# sfp_wrapper.net
KiCad netlist of a schematic drawn in Altium Designer
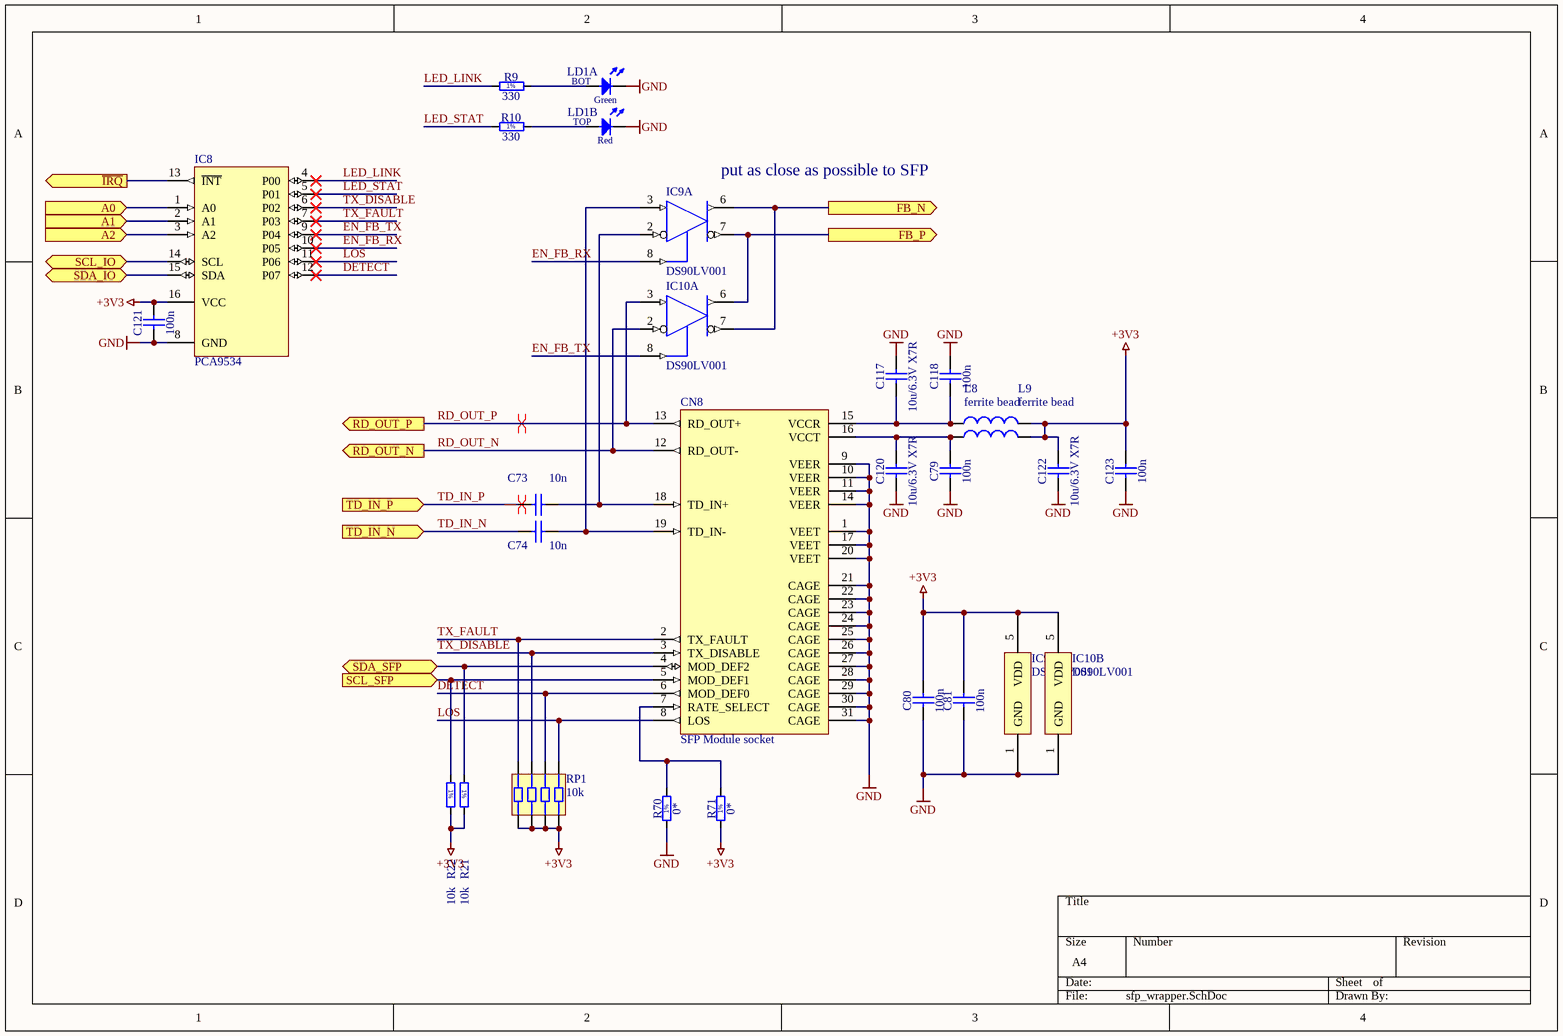
[diagram p0: sfp_wrapper.SchDoc]

(export (version "E")
  (design (tool "Eeschema 10.0.6"))
  (components
    (comp (ref "C73")
      (value "10n")
      (footprint "CAPC1608X87N")
      (description "Non-polarised capacitor")
      (fields
        (field (name "PART NUMBER") "CC0603_10NF_50V_10%_X7R")
        (field (name "VOLTAGE") "50V")
        (field (name "AUTHOR") "CERN DEM JLC")
      )
      (libsource (lib "Capacitors") (part "Capacitor - non polarized"))
    )
    (comp (ref "C74")
      (value "10n")
      (footprint "CAPC1608X87N")
      (description "Non-polarised capacitor")
      (fields
        (field (name "PART NUMBER") "CC0603_10NF_50V_10%_X7R")
        (field (name "VOLTAGE") "50V")
        (field (name "AUTHOR") "CERN DEM JLC")
      )
      (libsource (lib "Capacitors") (part "Capacitor - non polarized"))
    )
    (comp (ref "C79")
      (value "100n")
      (footprint "CAPC1608X87N")
      (description "Non-polarised capacitor")
      (fields
        (field (name "PART NUMBER") "CC0603_100NF_50V_10%_X7R")
        (field (name "VOLTAGE") "50V")
        (field (name "AUTHOR") "CERN DEM JLC")
      )
      (libsource (lib "Capacitors") (part "Capacitor - non polarized"))
    )
    (comp (ref "C80")
      (value "100n")
      (footprint "CAPC1608X87N")
      (description "Non-polarised capacitor")
      (fields
        (field (name "PART NUMBER") "CC0603_100NF_50V_10%_X7R")
        (field (name "VOLTAGE") "50V")
        (field (name "AUTHOR") "CERN DEM JLC")
      )
      (libsource (lib "Capacitors") (part "Capacitor - non polarized"))
    )
    (comp (ref "C81")
      (value "100n")
      (footprint "CAPC1608X87N")
      (description "Non-polarised capacitor")
      (fields
        (field (name "PART NUMBER") "CC0603_100NF_50V_10%_X7R")
        (field (name "VOLTAGE") "50V")
        (field (name "AUTHOR") "CERN DEM JLC")
      )
      (libsource (lib "Capacitors") (part "Capacitor - non polarized"))
    )
    (comp (ref "C117")
      (value "10u/6.3V X7R")
      (footprint "CAPC3216X140N")
      (description "Non-polarised capacitor")
      (fields
        (field (name "PART NUMBER") "CC1206_10UF_10V_10%_X7R")
        (field (name "VOLTAGE") "10V")
        (field (name "AUTHOR") "CERN DEM JLC")
      )
      (libsource (lib "Capacitors") (part "Capacitor - non polarized"))
    )
    (comp (ref "C118")
      (value "100n")
      (footprint "CAPC1608X87N")
      (description "Non-polarised capacitor")
      (fields
        (field (name "PART NUMBER") "CC0603_100NF_50V_10%_X7R")
        (field (name "VOLTAGE") "50V")
        (field (name "AUTHOR") "CERN DEM JLC")
      )
      (libsource (lib "Capacitors") (part "Capacitor - non polarized"))
    )
    (comp (ref "C120")
      (value "10u/6.3V X7R")
      (footprint "CAPC3216X140N")
      (description "Non-polarised capacitor")
      (fields
        (field (name "PART NUMBER") "CC1206_10UF_10V_10%_X7R")
        (field (name "VOLTAGE") "10V")
        (field (name "AUTHOR") "CERN DEM JLC")
      )
      (libsource (lib "Capacitors") (part "Capacitor - non polarized"))
    )
    (comp (ref "C121")
      (value "100n")
      (footprint "CAPC1608X87N")
      (description "Non-polarised capacitor")
      (fields
        (field (name "PART NUMBER") "CC0603_100NF_50V_10%_X7R")
        (field (name "VOLTAGE") "50V")
        (field (name "AUTHOR") "CERN DEM JLC")
      )
      (libsource (lib "Capacitors") (part "Capacitor - non polarized"))
    )
    (comp (ref "C122")
      (value "10u/6.3V X7R")
      (footprint "CAPC3216X140N")
      (description "Non-polarised capacitor")
      (fields
        (field (name "PART NUMBER") "CC1206_10UF_10V_10%_X7R")
        (field (name "VOLTAGE") "10V")
        (field (name "AUTHOR") "CERN DEM JLC")
      )
      (libsource (lib "Capacitors") (part "Capacitor - non polarized"))
    )
    (comp (ref "C123")
      (value "100n")
      (footprint "CAPC1608X87N")
      (description "Non-polarised capacitor")
      (fields
        (field (name "PART NUMBER") "CC0603_100NF_50V_10%_X7R")
        (field (name "VOLTAGE") "50V")
        (field (name "AUTHOR") "CERN DEM JLC")
      )
      (libsource (lib "Capacitors") (part "Capacitor - non polarized"))
    )
    (comp (ref "CN8")
      (value "SFP Module socket")
      (footprint "SFP_SINGLE_PORT")
      (description "Socket for SFP module")
      (libsource (lib "wr_switch") (part "SFP_SOCKET_SINGLE"))
    )
    (comp (ref "IC8")
      (value "PCA9534")
      (footprint "TSOP65P640-16AM")
      (description "8-bit I2C I/O expander")
      (libsource (lib "wr_switch") (part "PCA9534"))
    )
    (comp (ref "IC9")
      (value "DS90LV001")
      (footprint "SOIC127P600-8AL")
      (description "LVDS buffer with enable")
      (libsource (lib "wr_switch") (part "DS90LV001"))
    )
    (comp (ref "IC10")
      (value "DS90LV001")
      (footprint "SOIC127P600-8AL")
      (description "LVDS buffer with enable")
      (libsource (lib "wr_switch") (part "DS90LV001"))
    )
    (comp (ref "L8")
      (value "ferrite bead")
      (footprint "INDC2012-0805")
      (description "Ferrite bead")
      (fields (field (name "Comment") "Inductor") (field (name "PUBLISHER") "Altium Limited"))
      (libsource (lib "Miscellaneous Devices") (part "Inductor"))
    )
    (comp (ref "L9")
      (value "ferrite bead")
      (footprint "INDC2012-0805")
      (description "Ferrite bead")
      (fields (field (name "Comment") "Inductor") (field (name "PUBLISHER") "Altium Limited"))
      (libsource (lib "Miscellaneous Devices") (part "Inductor"))
    )
    (comp (ref "LD1")
      (value "Red/Green")
      (footprint "LED_DIALIGHT_571-0112-100F")
      (description "2x LED  Botom Green, Top Red")
      (fields
        (field (name "PART NUMBER") "LED_DIALIGHT_571-0112-100F")
        (field (name "MANUFACTURER") "DIALIGHT")
        (field (name "AUTHOR") "CERN DEM JLC")
      )
      (libsource (lib "ICs And Semiconductors") (part "LED x2 G-1C2A-BOT_R-3C4A-TOP"))
    )
    (comp (ref "R9")
      (value "330")
      (footprint "RESC1608X55N")
      (description "Resistor - 1%")
      (fields
        (field (name "PART NUMBER") "R0603_330R_1%_0.1W_100PPM")
        (field (name "POWER") "0.1W")
        (field (name "AUTHOR") "CERN DEM JLC")
      )
      (libsource (lib "Resistors") (part "Resistor - 1%"))
    )
    (comp (ref "R10")
      (value "330")
      (footprint "RESC1608X55N")
      (description "Resistor - 1%")
      (fields
        (field (name "PART NUMBER") "R0603_330R_1%_0.1W_100PPM")
        (field (name "POWER") "0.1W")
        (field (name "AUTHOR") "CERN DEM JLC")
      )
      (libsource (lib "Resistors") (part "Resistor - 1%"))
    )
    (comp (ref "R21")
      (value "10k")
      (footprint "RESC1608X55N")
      (description "Resistor - 1%")
      (fields
        (field (name "PART NUMBER") "R0603_10K_1%_0.1W_100PPM")
        (field (name "POWER") "0.1W")
        (field (name "AUTHOR") "CERN DEM JLC")
      )
      (libsource (lib "Resistors") (part "Resistor - 1%"))
    )
    (comp (ref "R22")
      (value "10k")
      (footprint "RESC1608X55N")
      (description "Resistor - 1%")
      (fields
        (field (name "PART NUMBER") "R0603_10K_1%_0.1W_100PPM")
        (field (name "POWER") "0.1W")
        (field (name "AUTHOR") "CERN DEM JLC")
      )
      (libsource (lib "Resistors") (part "Resistor - 1%"))
    )
    (comp (ref "R70")
      (value "0*")
      (footprint "RESC1608X55N")
      (description "Resistor - 1%")
      (fields
        (field (name "PART NUMBER") "R0603_0R_JUMPER")
        (field (name "MANUFACTURER") "GENERIC")
        (field (name "AUTHOR") "CERN DEM JLC")
      )
      (libsource (lib "Resistors") (part "Resistor - 1%"))
    )
    (comp (ref "R71")
      (value "0*")
      (footprint "RESC1608X55N")
      (description "Resistor - 1%")
      (fields
        (field (name "PART NUMBER") "R0603_0R_JUMPER")
        (field (name "MANUFACTURER") "GENERIC")
        (field (name "AUTHOR") "CERN DEM JLC")
      )
      (libsource (lib "Resistors") (part "Resistor - 1%"))
    )
    (comp (ref "RP1")
      (value "10k")
      (footprint "CAY-16")
      (description "Resistor network 1206 (4x0402) Maritex RAC4Xxxx")
      (libsource (lib "LIBRARY_SCH") (part "RES_ARRAY_1206"))
    )
  )
  (nets
    (net (code "1") (name "+3V3") (class "Default")
      (node (ref "C121") (pin "2") (pinfunction "2_2") (pintype "passive"))
      (node (ref "C122") (pin "2") (pinfunction "2_2") (pintype "passive"))
      (node (ref "C123") (pin "2") (pinfunction "2_2") (pintype "passive"))
      (node (ref "C80") (pin "2") (pinfunction "2_2") (pintype "passive"))
      (node (ref "C81") (pin "2") (pinfunction "2_2") (pintype "passive"))
      (node (ref "IC10") (pin "5") (pinfunction "VDD_5") (pintype "power_in"))
      (node (ref "IC8") (pin "16") (pinfunction "VCC_16") (pintype "power_in"))
      (node (ref "IC9") (pin "5") (pinfunction "VDD_5") (pintype "power_in"))
      (node (ref "L8") (pin "2") (pinfunction "2_2") (pintype "passive"))
      (node (ref "L9") (pin "2") (pinfunction "2_2") (pintype "passive"))
      (node (ref "R21") (pin "2") (pinfunction "2_2") (pintype "passive"))
      (node (ref "R22") (pin "2") (pinfunction "2_2") (pintype "passive"))
      (node (ref "R71") (pin "1") (pinfunction "1_1") (pintype "passive"))
      (node (ref "RP1") (pin "1") (pinfunction "1_1") (pintype "passive"))
      (node (ref "RP1") (pin "2") (pinfunction "2_2") (pintype "passive"))
      (node (ref "RP1") (pin "3") (pinfunction "3_3") (pintype "passive"))
      (node (ref "RP1") (pin "4") (pinfunction "4_4") (pintype "passive"))
    )
    (net (code "2") (name "/A0") (class "Default")
      (node (ref "IC8") (pin "1") (pinfunction "A0_1") (pintype "input"))
    )
    (net (code "3") (name "/A1") (class "Default")
      (node (ref "IC8") (pin "2") (pinfunction "A1_2") (pintype "input"))
    )
    (net (code "4") (name "/A2") (class "Default")
      (node (ref "IC8") (pin "3") (pinfunction "A2_3") (pintype "input"))
    )
    (net (code "5") (name "/DETECT") (class "Default")
      (node (ref "CN8") (pin "6") (pinfunction "MOD_DEF0_6") (pintype "output"))
      (node (ref "IC8") (pin "12") (pinfunction "P07_12") (pintype "bidirectional"))
      (node (ref "RP1") (pin "6") (pinfunction "6_6") (pintype "passive"))
    )
    (net (code "6") (name "/EN_FB_RX") (class "Default")
      (node (ref "IC8") (pin "10") (pinfunction "P05_10") (pintype "bidirectional"))
      (node (ref "IC9") (pin "8") (pinfunction "EN_8") (pintype "input"))
    )
    (net (code "7") (name "/EN_FB_TX") (class "Default")
      (node (ref "IC10") (pin "8") (pinfunction "EN_8") (pintype "input"))
      (node (ref "IC8") (pin "9") (pinfunction "P04_9") (pintype "bidirectional"))
    )
    (net (code "8") (name "/FB_N") (class "Default")
      (node (ref "IC10") (pin "7") (pinfunction "OUT-_7") (pintype "output"))
      (node (ref "IC9") (pin "6") (pinfunction "OUT+_6") (pintype "output"))
    )
    (net (code "9") (name "/FB_P") (class "Default")
      (node (ref "IC10") (pin "6") (pinfunction "OUT+_6") (pintype "output"))
      (node (ref "IC9") (pin "7") (pinfunction "OUT-_7") (pintype "output"))
    )
    (net (code "10") (name "/LED_LINK") (class "Default")
      (node (ref "IC8") (pin "4") (pinfunction "P00_4") (pintype "bidirectional"))
      (node (ref "R9") (pin "1") (pinfunction "1_1") (pintype "passive"))
    )
    (net (code "11") (name "/LED_STAT") (class "Default")
      (node (ref "IC8") (pin "5") (pinfunction "P01_5") (pintype "bidirectional"))
      (node (ref "R10") (pin "1") (pinfunction "1_1") (pintype "passive"))
    )
    (net (code "12") (name "/LOS") (class "Default")
      (node (ref "CN8") (pin "8") (pinfunction "LOS_8") (pintype "output"))
      (node (ref "IC8") (pin "11") (pinfunction "P06_11") (pintype "bidirectional"))
      (node (ref "RP1") (pin "5") (pinfunction "5_5") (pintype "passive"))
    )
    (net (code "13") (name "/RD_OUT_N") (class "Default")
      (node (ref "CN8") (pin "12") (pinfunction "RD_OUT-_12") (pintype "output"))
      (node (ref "IC10") (pin "2") (pinfunction "IN-_2") (pintype "input"))
    )
    (net (code "14") (name "/RD_OUT_P") (class "Default")
      (node (ref "CN8") (pin "13") (pinfunction "RD_OUT+_13") (pintype "output"))
      (node (ref "IC10") (pin "3") (pinfunction "IN+_3") (pintype "input"))
    )
    (net (code "15") (name "/SCL_IO") (class "Default")
      (node (ref "IC8") (pin "14") (pinfunction "SCL_14") (pintype "bidirectional"))
    )
    (net (code "16") (name "/SCL_SFP") (class "Default")
      (node (ref "CN8") (pin "5") (pinfunction "MOD_DEF1_5") (pintype "input"))
      (node (ref "R22") (pin "1") (pinfunction "1_1") (pintype "passive"))
    )
    (net (code "17") (name "/SDA_IO") (class "Default")
      (node (ref "IC8") (pin "15") (pinfunction "SDA_15") (pintype "bidirectional"))
    )
    (net (code "18") (name "/SDA_SFP") (class "Default")
      (node (ref "CN8") (pin "4") (pinfunction "MOD_DEF2_4") (pintype "bidirectional"))
      (node (ref "R21") (pin "1") (pinfunction "1_1") (pintype "passive"))
    )
    (net (code "19") (name "/TD_IN_N") (class "Default")
      (node (ref "C74") (pin "1") (pinfunction "1_1") (pintype "passive"))
    )
    (net (code "20") (name "/TD_IN_P") (class "Default")
      (node (ref "C73") (pin "1") (pinfunction "1_1") (pintype "passive"))
    )
    (net (code "21") (name "/TX_DISABLE") (class "Default")
      (node (ref "CN8") (pin "3") (pinfunction "TX_DISABLE_3") (pintype "input"))
      (node (ref "IC8") (pin "6") (pinfunction "P02_6") (pintype "bidirectional"))
      (node (ref "RP1") (pin "7") (pinfunction "7_7") (pintype "passive"))
    )
    (net (code "22") (name "/TX_FAULT") (class "Default")
      (node (ref "CN8") (pin "2") (pinfunction "TX_FAULT_2") (pintype "output"))
      (node (ref "IC8") (pin "7") (pinfunction "P03_7") (pintype "bidirectional"))
      (node (ref "RP1") (pin "8") (pinfunction "8_8") (pintype "passive"))
    )
    (net (code "23") (name "/~{IRQ}") (class "Default")
      (node (ref "IC8") (pin "13") (pinfunction "~{INT}_13") (pintype "output"))
    )
    (net (code "24") (name "GND") (class "Default")
      (node (ref "C117") (pin "2") (pinfunction "2_2") (pintype "passive"))
      (node (ref "C118") (pin "2") (pinfunction "2_2") (pintype "passive"))
      (node (ref "C120") (pin "1") (pinfunction "1_1") (pintype "passive"))
      (node (ref "C121") (pin "1") (pinfunction "1_1") (pintype "passive"))
      (node (ref "C122") (pin "1") (pinfunction "1_1") (pintype "passive"))
      (node (ref "C123") (pin "1") (pinfunction "1_1") (pintype "passive"))
      (node (ref "C79") (pin "1") (pinfunction "1_1") (pintype "passive"))
      (node (ref "C80") (pin "1") (pinfunction "1_1") (pintype "passive"))
      (node (ref "C81") (pin "1") (pinfunction "1_1") (pintype "passive"))
      (node (ref "CN8") (pin "1") (pinfunction "VEET_1") (pintype "power_in"))
      (node (ref "CN8") (pin "10") (pinfunction "VEER_10") (pintype "power_in"))
      (node (ref "CN8") (pin "11") (pinfunction "VEER_11") (pintype "power_in"))
      (node (ref "CN8") (pin "14") (pinfunction "VEER_14") (pintype "power_in"))
      (node (ref "CN8") (pin "17") (pinfunction "VEET_17") (pintype "power_in"))
      (node (ref "CN8") (pin "20") (pinfunction "VEET_20") (pintype "power_in"))
      (node (ref "CN8") (pin "21") (pinfunction "CAGE_21") (pintype "power_in"))
      (node (ref "CN8") (pin "22") (pinfunction "CAGE_22") (pintype "power_in"))
      (node (ref "CN8") (pin "23") (pinfunction "CAGE_23") (pintype "power_in"))
      (node (ref "CN8") (pin "24") (pinfunction "CAGE_24") (pintype "power_in"))
      (node (ref "CN8") (pin "25") (pinfunction "CAGE_25") (pintype "power_in"))
      (node (ref "CN8") (pin "26") (pinfunction "CAGE_26") (pintype "power_in"))
      (node (ref "CN8") (pin "27") (pinfunction "CAGE_27") (pintype "power_in"))
      (node (ref "CN8") (pin "28") (pinfunction "CAGE_28") (pintype "power_in"))
      (node (ref "CN8") (pin "29") (pinfunction "CAGE_29") (pintype "power_in"))
      (node (ref "CN8") (pin "30") (pinfunction "CAGE_30") (pintype "power_in"))
      (node (ref "CN8") (pin "31") (pinfunction "CAGE_31") (pintype "power_in"))
      (node (ref "CN8") (pin "9") (pinfunction "VEER_9") (pintype "power_in"))
      (node (ref "IC10") (pin "1") (pinfunction "GND_1") (pintype "power_in"))
      (node (ref "IC8") (pin "8") (pinfunction "GND_8") (pintype "power_in"))
      (node (ref "IC9") (pin "1") (pinfunction "GND_1") (pintype "power_in"))
      (node (ref "LD1") (pin "1") (pinfunction "C_1") (pintype "passive"))
      (node (ref "LD1") (pin "3") (pinfunction "C_3") (pintype "passive"))
      (node (ref "R70") (pin "1") (pinfunction "1_1") (pintype "passive"))
    )
    (net (code "25") (name "Net-(CN8-RATE_SELECT)") (class "Default")
      (node (ref "CN8") (pin "7") (pinfunction "RATE_SELECT_7") (pintype "input"))
      (node (ref "R70") (pin "2") (pinfunction "2_2") (pintype "passive"))
      (node (ref "R71") (pin "2") (pinfunction "2_2") (pintype "passive"))
    )
    (net (code "26") (name "Net-(CN8-TD_IN+)") (class "Default")
      (node (ref "C73") (pin "2") (pinfunction "2_2") (pintype "passive"))
      (node (ref "CN8") (pin "18") (pinfunction "TD_IN+_18") (pintype "input"))
      (node (ref "IC9") (pin "2") (pinfunction "IN-_2") (pintype "input"))
    )
    (net (code "27") (name "Net-(CN8-TD_IN-)") (class "Default")
      (node (ref "C74") (pin "2") (pinfunction "2_2") (pintype "passive"))
      (node (ref "CN8") (pin "19") (pinfunction "TD_IN-_19") (pintype "input"))
      (node (ref "IC9") (pin "3") (pinfunction "IN+_3") (pintype "input"))
    )
    (net (code "28") (name "Net-(CN8-VCCR)") (class "Default")
      (node (ref "C117") (pin "1") (pinfunction "1_1") (pintype "passive"))
      (node (ref "C118") (pin "1") (pinfunction "1_1") (pintype "passive"))
      (node (ref "CN8") (pin "15") (pinfunction "VCCR_15") (pintype "power_in"))
      (node (ref "L9") (pin "1") (pinfunction "1_1") (pintype "passive"))
    )
    (net (code "29") (name "Net-(CN8-VCCT)") (class "Default")
      (node (ref "C120") (pin "2") (pinfunction "2_2") (pintype "passive"))
      (node (ref "C79") (pin "2") (pinfunction "2_2") (pintype "passive"))
      (node (ref "CN8") (pin "16") (pinfunction "VCCT_16") (pintype "power_in"))
      (node (ref "L8") (pin "1") (pinfunction "1_1") (pintype "passive"))
    )
    (net (code "30") (name "Net-(LD1A-A)") (class "Default")
      (node (ref "LD1") (pin "2") (pinfunction "A_2") (pintype "passive"))
      (node (ref "R9") (pin "2") (pinfunction "2_2") (pintype "passive"))
    )
    (net (code "31") (name "Net-(LD1B-A)") (class "Default")
      (node (ref "LD1") (pin "4") (pinfunction "A_4") (pintype "passive"))
      (node (ref "R10") (pin "2") (pinfunction "2_2") (pintype "passive"))
    )
  )
)
